# E17-PDU-LOAD_3.net
KiCad netlist of a schematic drawn in Altium Designer
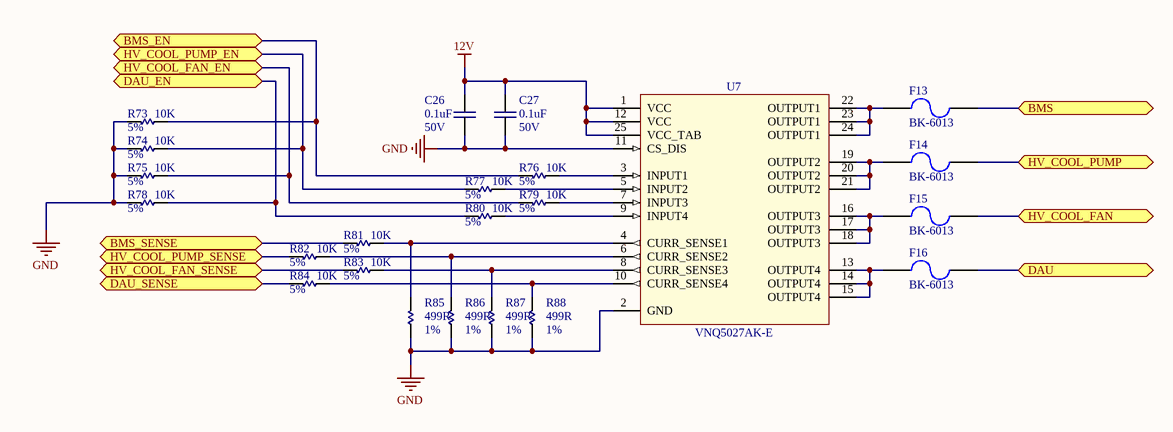
[diagram p0: E17-PDU-LOAD_3.SchDoc]

(export (version "E")
  (design (tool "Eeschema 10.0.6"))
  (components
    (comp (ref "C26")
      (value "0.1uF")
      (footprint "C0805")
      (description "Generic 0805 Capacitor")
      (fields
        (field (name "TOLERANCE") "10%")
        (field (name "VOLTAGE") "50V")
        (field (name "Comment") "C_0805_Generic")
      )
      (libsource (lib "Compiled_PDU") (part "C_0805_Generic"))
    )
    (comp (ref "C27")
      (value "0.1uF")
      (footprint "C0805")
      (description "Generic 0805 Capacitor")
      (fields
        (field (name "TOLERANCE") "10%")
        (field (name "VOLTAGE") "50V")
        (field (name "Comment") "C_0805_Generic")
      )
      (libsource (lib "Compiled_PDU") (part "C_0805_Generic"))
    )
    (comp (ref "F13")
      (value "F_BK-6013")
      (footprint "BK-6013")
      (description "FUSE HOLDER BLADE PCB")
      (fields (field (name "MFG") "MPD") (field (name "MFG_PN") "BK-6013"))
      (libsource (lib "Compiled_PDU") (part "F_BK-6013"))
    )
    (comp (ref "F14")
      (value "F_BK-6013")
      (footprint "BK-6013")
      (description "FUSE HOLDER BLADE PCB")
      (fields (field (name "MFG") "MPD") (field (name "MFG_PN") "BK-6013"))
      (libsource (lib "Compiled_PDU") (part "F_BK-6013"))
    )
    (comp (ref "F15")
      (value "F_BK-6013")
      (footprint "BK-6013")
      (description "FUSE HOLDER BLADE PCB")
      (fields (field (name "MFG") "MPD") (field (name "MFG_PN") "BK-6013"))
      (libsource (lib "Compiled_PDU") (part "F_BK-6013"))
    )
    (comp (ref "F16")
      (value "F_BK-6013")
      (footprint "BK-6013")
      (description "FUSE HOLDER BLADE PCB")
      (fields (field (name "MFG") "MPD") (field (name "MFG_PN") "BK-6013"))
      (libsource (lib "Compiled_PDU") (part "F_BK-6013"))
    )
    (comp (ref "R73")
      (value "10K")
      (footprint "R0603")
      (description "Generic 0603 Resistor")
      (fields
        (field (name "POWER") "1/10W")
        (field (name "TOLERANCE") "5%")
        (field (name "Comment") "R_0603_Generic")
      )
      (libsource (lib "Compiled_PDU") (part "R_0603_Generic"))
    )
    (comp (ref "R74")
      (value "10K")
      (footprint "R0603")
      (description "Generic 0603 Resistor")
      (fields
        (field (name "POWER") "1/10W")
        (field (name "TOLERANCE") "5%")
        (field (name "Comment") "R_0603_Generic")
      )
      (libsource (lib "Compiled_PDU") (part "R_0603_Generic"))
    )
    (comp (ref "R75")
      (value "10K")
      (footprint "R0603")
      (description "Generic 0603 Resistor")
      (fields
        (field (name "POWER") "1/10W")
        (field (name "TOLERANCE") "5%")
        (field (name "Comment") "R_0603_Generic")
      )
      (libsource (lib "Compiled_PDU") (part "R_0603_Generic"))
    )
    (comp (ref "R76")
      (value "10K")
      (footprint "R0603")
      (description "Generic 0603 Resistor")
      (fields
        (field (name "POWER") "1/10W")
        (field (name "TOLERANCE") "5%")
        (field (name "Comment") "R_0603_Generic")
      )
      (libsource (lib "Compiled_PDU") (part "R_0603_Generic"))
    )
    (comp (ref "R77")
      (value "10K")
      (footprint "R0603")
      (description "Generic 0603 Resistor")
      (fields
        (field (name "POWER") "1/10W")
        (field (name "TOLERANCE") "5%")
        (field (name "Comment") "R_0603_Generic")
      )
      (libsource (lib "Compiled_PDU") (part "R_0603_Generic"))
    )
    (comp (ref "R78")
      (value "10K")
      (footprint "R0603")
      (description "Generic 0603 Resistor")
      (fields
        (field (name "POWER") "1/10W")
        (field (name "TOLERANCE") "5%")
        (field (name "Comment") "R_0603_Generic")
      )
      (libsource (lib "Compiled_PDU") (part "R_0603_Generic"))
    )
    (comp (ref "R79")
      (value "10K")
      (footprint "R0603")
      (description "Generic 0603 Resistor")
      (fields
        (field (name "POWER") "1/10W")
        (field (name "TOLERANCE") "5%")
        (field (name "Comment") "R_0603_Generic")
      )
      (libsource (lib "Compiled_PDU") (part "R_0603_Generic"))
    )
    (comp (ref "R80")
      (value "10K")
      (footprint "R0603")
      (description "Generic 0603 Resistor")
      (fields
        (field (name "POWER") "1/10W")
        (field (name "TOLERANCE") "5%")
        (field (name "Comment") "R_0603_Generic")
      )
      (libsource (lib "Compiled_PDU") (part "R_0603_Generic"))
    )
    (comp (ref "R81")
      (value "10K")
      (footprint "R0603")
      (description "Generic 0603 Resistor")
      (fields
        (field (name "POWER") "1/10W")
        (field (name "TOLERANCE") "5%")
        (field (name "Comment") "R_0603_Generic")
      )
      (libsource (lib "Compiled_PDU") (part "R_0603_Generic"))
    )
    (comp (ref "R82")
      (value "10K")
      (footprint "R0603")
      (description "Generic 0603 Resistor")
      (fields
        (field (name "POWER") "1/10W")
        (field (name "TOLERANCE") "5%")
        (field (name "Comment") "R_0603_Generic")
      )
      (libsource (lib "Compiled_PDU") (part "R_0603_Generic"))
    )
    (comp (ref "R83")
      (value "10K")
      (footprint "R0603")
      (description "Generic 0603 Resistor")
      (fields
        (field (name "POWER") "1/10W")
        (field (name "TOLERANCE") "5%")
        (field (name "Comment") "R_0603_Generic")
      )
      (libsource (lib "Compiled_PDU") (part "R_0603_Generic"))
    )
    (comp (ref "R84")
      (value "10K")
      (footprint "R0603")
      (description "Generic 0603 Resistor")
      (fields
        (field (name "POWER") "1/10W")
        (field (name "TOLERANCE") "5%")
        (field (name "Comment") "R_0603_Generic")
      )
      (libsource (lib "Compiled_PDU") (part "R_0603_Generic"))
    )
    (comp (ref "R85")
      (value "499R")
      (footprint "R0603")
      (description "Generic 0603 Resistor")
      (fields
        (field (name "POWER") "1/8W")
        (field (name "TOLERANCE") "1%")
        (field (name "Comment") "R_0603_Generic")
      )
      (libsource (lib "Compiled_PDU") (part "R_0603_Generic"))
    )
    (comp (ref "R86")
      (value "499R")
      (footprint "R0603")
      (description "Generic 0603 Resistor")
      (fields
        (field (name "POWER") "1/8W")
        (field (name "TOLERANCE") "1%")
        (field (name "Comment") "R_0603_Generic")
      )
      (libsource (lib "Compiled_PDU") (part "R_0603_Generic"))
    )
    (comp (ref "R87")
      (value "499R")
      (footprint "R0603")
      (description "Generic 0603 Resistor")
      (fields
        (field (name "POWER") "1/8W")
        (field (name "TOLERANCE") "1%")
        (field (name "Comment") "R_0603_Generic")
      )
      (libsource (lib "Compiled_PDU") (part "R_0603_Generic"))
    )
    (comp (ref "R88")
      (value "499R")
      (footprint "R0603")
      (description "Generic 0603 Resistor")
      (fields
        (field (name "POWER") "1/8W")
        (field (name "TOLERANCE") "1%")
        (field (name "Comment") "R_0603_Generic")
      )
      (libsource (lib "Compiled_PDU") (part "R_0603_Generic"))
    )
    (comp (ref "U7")
      (value "U_VNQ5027AK-E")
      (footprint "PowerSSO-24")
      (description "LOAD CHANNEL HIGH SIDE 42A 4 Channel")
      (fields (field (name "MFG") "STmicroelectronics") (field (name "MFG_PN") "VNQ5027AK-E"))
      (libsource (lib "Compiled_PDU") (part "U_VNQ5027AK-E"))
    )
  )
  (nets
    (net (code "1") (name "/BMS") (class "Default")
      (node (ref "F13") (pin "2") (pinfunction "2_2") (pintype "passive"))
    )
    (net (code "2") (name "/BMS_EN") (class "Default")
      (node (ref "R73") (pin "2") (pinfunction "2_2") (pintype "passive"))
      (node (ref "R76") (pin "1") (pinfunction "1_1") (pintype "passive"))
    )
    (net (code "3") (name "/BMS_SENSE") (class "Default")
      (node (ref "R81") (pin "1") (pinfunction "1_1") (pintype "passive"))
    )
    (net (code "4") (name "/DAU") (class "Default")
      (node (ref "F16") (pin "2") (pinfunction "2_2") (pintype "passive"))
    )
    (net (code "5") (name "/DAU_EN") (class "Default")
      (node (ref "R78") (pin "2") (pinfunction "2_2") (pintype "passive"))
      (node (ref "R80") (pin "1") (pinfunction "1_1") (pintype "passive"))
    )
    (net (code "6") (name "/DAU_SENSE") (class "Default")
      (node (ref "R84") (pin "1") (pinfunction "1_1") (pintype "passive"))
    )
    (net (code "7") (name "/HV_COOL_FAN") (class "Default")
      (node (ref "F15") (pin "2") (pinfunction "2_2") (pintype "passive"))
    )
    (net (code "8") (name "/HV_COOL_FAN_EN") (class "Default")
      (node (ref "R75") (pin "2") (pinfunction "2_2") (pintype "passive"))
      (node (ref "R79") (pin "1") (pinfunction "1_1") (pintype "passive"))
    )
    (net (code "9") (name "/HV_COOL_FAN_SENSE") (class "Default")
      (node (ref "R83") (pin "1") (pinfunction "1_1") (pintype "passive"))
    )
    (net (code "10") (name "/HV_COOL_PUMP") (class "Default")
      (node (ref "F14") (pin "2") (pinfunction "2_2") (pintype "passive"))
    )
    (net (code "11") (name "/HV_COOL_PUMP_EN") (class "Default")
      (node (ref "R74") (pin "2") (pinfunction "2_2") (pintype "passive"))
      (node (ref "R77") (pin "1") (pinfunction "1_1") (pintype "passive"))
    )
    (net (code "12") (name "/HV_COOL_PUMP_SENSE") (class "Default")
      (node (ref "R82") (pin "1") (pinfunction "1_1") (pintype "passive"))
    )
    (net (code "13") (name "12V") (class "Default")
      (node (ref "C26") (pin "1") (pinfunction "EGND_1") (pintype "passive"))
      (node (ref "C27") (pin "1") (pinfunction "EGND_1") (pintype "passive"))
      (node (ref "U7") (pin "1") (pinfunction "VCC_1") (pintype "power_in"))
      (node (ref "U7") (pin "12") (pinfunction "VCC_12") (pintype "power_in"))
      (node (ref "U7") (pin "25") (pinfunction "VCC_TAB_25") (pintype "power_in"))
    )
    (net (code "14") (name "GND") (class "Default")
      (node (ref "C26") (pin "2") (pinfunction "2_2") (pintype "passive"))
      (node (ref "C27") (pin "2") (pinfunction "2_2") (pintype "passive"))
      (node (ref "R73") (pin "1") (pinfunction "1_1") (pintype "passive"))
      (node (ref "R74") (pin "1") (pinfunction "1_1") (pintype "passive"))
      (node (ref "R75") (pin "1") (pinfunction "1_1") (pintype "passive"))
      (node (ref "R78") (pin "1") (pinfunction "1_1") (pintype "passive"))
      (node (ref "R85") (pin "2") (pinfunction "2_2") (pintype "passive"))
      (node (ref "R86") (pin "2") (pinfunction "2_2") (pintype "passive"))
      (node (ref "R87") (pin "2") (pinfunction "2_2") (pintype "passive"))
      (node (ref "R88") (pin "2") (pinfunction "2_2") (pintype "passive"))
      (node (ref "U7") (pin "11") (pinfunction "CS_DIS_11") (pintype "input"))
      (node (ref "U7") (pin "2") (pinfunction "GND_2") (pintype "power_in"))
    )
    (net (code "15") (name "Net-(F13-Pad1)") (class "Default")
      (node (ref "F13") (pin "1") (pinfunction "1_1") (pintype "passive"))
      (node (ref "U7") (pin "22") (pinfunction "OUTPUT1_22") (pintype "power_in"))
      (node (ref "U7") (pin "23") (pinfunction "OUTPUT1_23") (pintype "power_in"))
      (node (ref "U7") (pin "24") (pinfunction "OUTPUT1_24") (pintype "power_in"))
    )
    (net (code "16") (name "Net-(F14-Pad1)") (class "Default")
      (node (ref "F14") (pin "1") (pinfunction "1_1") (pintype "passive"))
      (node (ref "U7") (pin "19") (pinfunction "OUTPUT2_19") (pintype "power_in"))
      (node (ref "U7") (pin "20") (pinfunction "OUTPUT2_20") (pintype "power_in"))
      (node (ref "U7") (pin "21") (pinfunction "OUTPUT2_21") (pintype "power_in"))
    )
    (net (code "17") (name "Net-(F15-Pad1)") (class "Default")
      (node (ref "F15") (pin "1") (pinfunction "1_1") (pintype "passive"))
      (node (ref "U7") (pin "16") (pinfunction "OUTPUT3_16") (pintype "power_in"))
      (node (ref "U7") (pin "17") (pinfunction "OUTPUT3_17") (pintype "power_in"))
      (node (ref "U7") (pin "18") (pinfunction "OUTPUT3_18") (pintype "power_in"))
    )
    (net (code "18") (name "Net-(F16-Pad1)") (class "Default")
      (node (ref "F16") (pin "1") (pinfunction "1_1") (pintype "passive"))
      (node (ref "U7") (pin "13") (pinfunction "OUTPUT4_13") (pintype "power_in"))
      (node (ref "U7") (pin "14") (pinfunction "OUTPUT4_14") (pintype "power_in"))
      (node (ref "U7") (pin "15") (pinfunction "OUTPUT4_15") (pintype "power_in"))
    )
    (net (code "19") (name "Net-(U7-CURR_SENSE1)") (class "Default")
      (node (ref "R81") (pin "2") (pinfunction "2_2") (pintype "passive"))
      (node (ref "R85") (pin "1") (pinfunction "1_1") (pintype "passive"))
      (node (ref "U7") (pin "4") (pinfunction "CURR_SENSE1_4") (pintype "output"))
    )
    (net (code "20") (name "Net-(U7-CURR_SENSE2)") (class "Default")
      (node (ref "R82") (pin "2") (pinfunction "2_2") (pintype "passive"))
      (node (ref "R86") (pin "1") (pinfunction "1_1") (pintype "passive"))
      (node (ref "U7") (pin "6") (pinfunction "CURR_SENSE2_6") (pintype "output"))
    )
    (net (code "21") (name "Net-(U7-CURR_SENSE3)") (class "Default")
      (node (ref "R83") (pin "2") (pinfunction "2_2") (pintype "passive"))
      (node (ref "R87") (pin "1") (pinfunction "1_1") (pintype "passive"))
      (node (ref "U7") (pin "8") (pinfunction "CURR_SENSE3_8") (pintype "output"))
    )
    (net (code "22") (name "Net-(U7-CURR_SENSE4)") (class "Default")
      (node (ref "R84") (pin "2") (pinfunction "2_2") (pintype "passive"))
      (node (ref "R88") (pin "1") (pinfunction "1_1") (pintype "passive"))
      (node (ref "U7") (pin "10") (pinfunction "CURR_SENSE4_10") (pintype "output"))
    )
    (net (code "23") (name "Net-(U7-INPUT1)") (class "Default")
      (node (ref "R76") (pin "2") (pinfunction "2_2") (pintype "passive"))
      (node (ref "U7") (pin "3") (pinfunction "INPUT1_3") (pintype "input"))
    )
    (net (code "24") (name "Net-(U7-INPUT2)") (class "Default")
      (node (ref "R77") (pin "2") (pinfunction "2_2") (pintype "passive"))
      (node (ref "U7") (pin "5") (pinfunction "INPUT2_5") (pintype "input"))
    )
    (net (code "25") (name "Net-(U7-INPUT3)") (class "Default")
      (node (ref "R79") (pin "2") (pinfunction "2_2") (pintype "passive"))
      (node (ref "U7") (pin "7") (pinfunction "INPUT3_7") (pintype "input"))
    )
    (net (code "26") (name "Net-(U7-INPUT4)") (class "Default")
      (node (ref "R80") (pin "2") (pinfunction "2_2") (pintype "passive"))
      (node (ref "U7") (pin "9") (pinfunction "INPUT4_9") (pintype "input"))
    )
  )
)
